# rat2.net
KiCad netlist of a schematic drawn in EAGLE
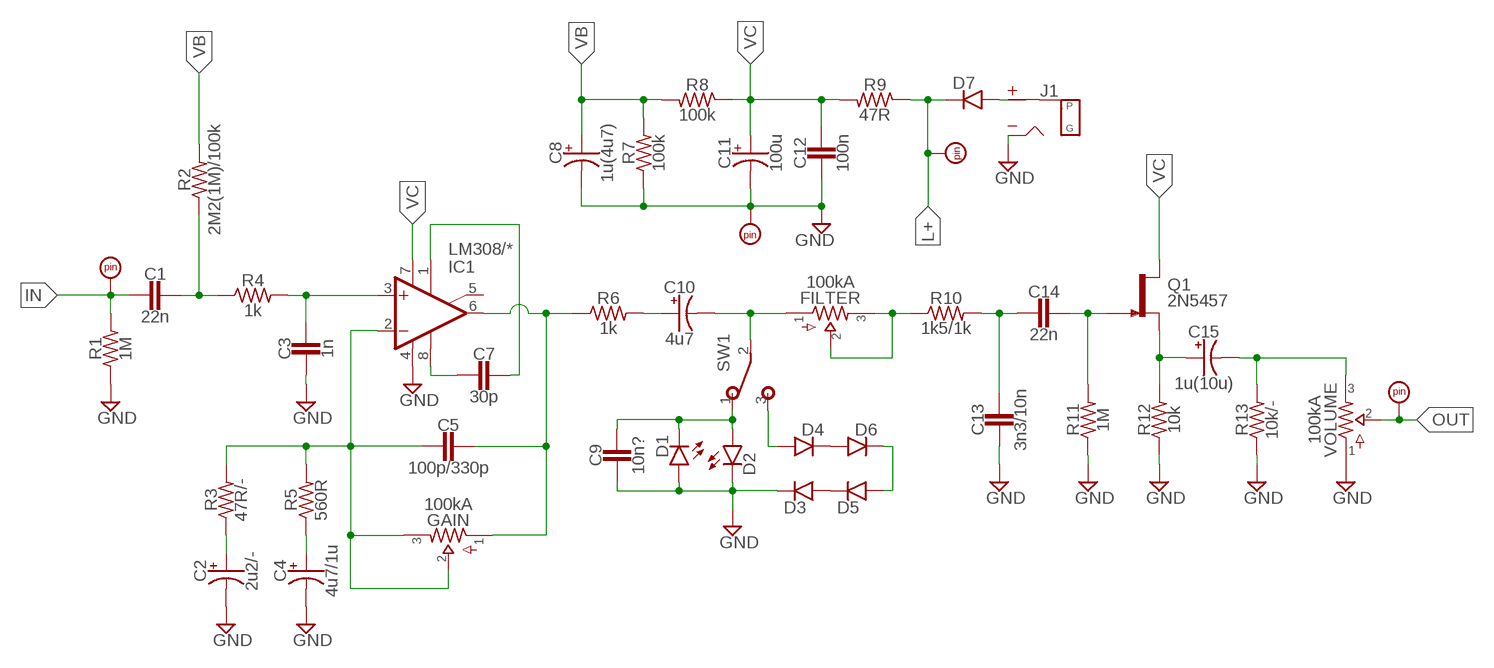
[diagram p0: schematic, sheet 1]

(export (version "E")
  (design (tool "Eeschema 10.0.6"))
  (components
    (comp (ref "C1")
      (value "22n")
      (footprint "eagle-import:050X030_025_2")
      (libsource (lib "eagle-import") (part "CER/FILM2"))
    )
    (comp (ref "C2")
      (value "2u2/-")
      (footprint "eagle-import:050_020_1")
      (libsource (lib "eagle-import") (part "0501"))
    )
    (comp (ref "C3")
      (value "1n")
      (footprint "eagle-import:050X030_025_2")
      (libsource (lib "eagle-import") (part "CER/FILM2"))
    )
    (comp (ref "C4")
      (value "4u7/1u")
      (footprint "eagle-import:050_020_1")
      (libsource (lib "eagle-import") (part "0501"))
    )
    (comp (ref "C5")
      (value "100p/330p")
      (footprint "eagle-import:050X030_025_2")
      (libsource (lib "eagle-import") (part "CER/FILM2"))
    )
    (comp (ref "C7")
      (value "30p")
      (footprint "eagle-import:050X030_025_2")
      (libsource (lib "eagle-import") (part "CER/FILM2"))
    )
    (comp (ref "C8")
      (value "1u(4u7)")
      (footprint "eagle-import:050_020_1")
      (libsource (lib "eagle-import") (part "0501"))
    )
    (comp (ref "C9")
      (value "10n?")
      (footprint "eagle-import:050X030_025_2")
      (libsource (lib "eagle-import") (part "CER/FILM2"))
    )
    (comp (ref "C10")
      (value "4u7")
      (footprint "eagle-import:050_020_1")
      (libsource (lib "eagle-import") (part "0501"))
    )
    (comp (ref "C11")
      (value "100u")
      (footprint "eagle-import:050_020_1")
      (libsource (lib "eagle-import") (part "0501"))
    )
    (comp (ref "C12")
      (value "100n")
      (footprint "eagle-import:050X030_025_2")
      (libsource (lib "eagle-import") (part "CER/FILM2"))
    )
    (comp (ref "C13")
      (value "3n3/10n")
      (footprint "eagle-import:050X030_025_2")
      (libsource (lib "eagle-import") (part "CER/FILM2"))
    )
    (comp (ref "C14")
      (value "22n")
      (footprint "eagle-import:050X030_025_2")
      (libsource (lib "eagle-import") (part "CER/FILM2"))
    )
    (comp (ref "C15")
      (value "1u(10u)")
      (footprint "eagle-import:050_020_1")
      (libsource (lib "eagle-import") (part "0501"))
    )
    (comp (ref "D1")
      (value "LEDB")
      (footprint "eagle-import:3MM_B")
      (libsource (lib "eagle-import") (part "LEDB"))
    )
    (comp (ref "D2")
      (value "LEDB")
      (footprint "eagle-import:3MM_B")
      (libsource (lib "eagle-import") (part "LEDB"))
    )
    (comp (ref "D3")
      (value "DO35.3")
      (footprint "eagle-import:DO35-3")
      (libsource (lib "eagle-import") (part "DO35.3"))
    )
    (comp (ref "D4")
      (value "DO35.3")
      (footprint "eagle-import:DO35-3")
      (libsource (lib "eagle-import") (part "DO35.3"))
    )
    (comp (ref "D5")
      (value "DO35.3")
      (footprint "eagle-import:DO35-3")
      (libsource (lib "eagle-import") (part "DO35.3"))
    )
    (comp (ref "D6")
      (value "DO35.3")
      (footprint "eagle-import:DO35-3")
      (libsource (lib "eagle-import") (part "DO35.3"))
    )
    (comp (ref "D7")
      (value "DO41.3")
      (footprint "eagle-import:DO41-3")
      (libsource (lib "eagle-import") (part "DO41.3"))
    )
    (comp (ref "FILTER")
      (value "100kA")
      (footprint "eagle-import:16MM")
      (libsource (lib "eagle-import") (part "POTS16MM"))
    )
    (comp (ref "GAIN")
      (value "100kA")
      (footprint "eagle-import:16MM")
      (libsource (lib "eagle-import") (part "POTS16MM"))
    )
    (comp (ref "IC1")
      (value "LM308/*")
      (footprint "eagle-import:DIL08")
      (libsource (lib "eagle-import") (part "SINGLETH"))
    )
    (comp (ref "J1")
      (value "DC_MONO")
      (footprint "eagle-import:DC")
      (libsource (lib "eagle-import") (part "DC_MONO"))
    )
    (comp (ref "PAD1")
      (value "PADSQR")
      (footprint "eagle-import:SQUARE")
      (libsource (lib "eagle-import") (part "PADSQR"))
    )
    (comp (ref "PAD2")
      (value "PADRND")
      (footprint "eagle-import:ROUND")
      (libsource (lib "eagle-import") (part "PADRND"))
    )
    (comp (ref "PAD3")
      (value "PADSQR")
      (footprint "eagle-import:SQUARE")
      (libsource (lib "eagle-import") (part "PADSQR"))
    )
    (comp (ref "PAD4")
      (value "PADSQR")
      (footprint "eagle-import:SQUARE")
      (libsource (lib "eagle-import") (part "PADSQR"))
    )
    (comp (ref "Q1")
      (value "2N5457")
      (footprint "eagle-import:TO92-")
      (libsource (lib "eagle-import") (part "2N5457"))
    )
    (comp (ref "R1")
      (value "1M")
      (footprint "eagle-import:R0207_3")
      (libsource (lib "eagle-import") (part "R_.3B"))
    )
    (comp (ref "R2")
      (value "2M2(1M)/100k")
      (footprint "eagle-import:R0207_3")
      (libsource (lib "eagle-import") (part "R_.3B"))
    )
    (comp (ref "R3")
      (value "47R/-")
      (footprint "eagle-import:R0207_3")
      (libsource (lib "eagle-import") (part "R_.3B"))
    )
    (comp (ref "R4")
      (value "1k")
      (footprint "eagle-import:R0207_3")
      (libsource (lib "eagle-import") (part "R_.3B"))
    )
    (comp (ref "R5")
      (value "560R")
      (footprint "eagle-import:R0207_3")
      (libsource (lib "eagle-import") (part "R_.3B"))
    )
    (comp (ref "R6")
      (value "1k")
      (footprint "eagle-import:R0207_3")
      (libsource (lib "eagle-import") (part "R_.3B"))
    )
    (comp (ref "R7")
      (value "100k")
      (footprint "eagle-import:R0207_3")
      (libsource (lib "eagle-import") (part "R_.3B"))
    )
    (comp (ref "R8")
      (value "100k")
      (footprint "eagle-import:R0207_3")
      (libsource (lib "eagle-import") (part "R_.3B"))
    )
    (comp (ref "R9")
      (value "47R")
      (footprint "eagle-import:R0207_3")
      (libsource (lib "eagle-import") (part "R_.3B"))
    )
    (comp (ref "R10")
      (value "1k5/1k")
      (footprint "eagle-import:R0207_3")
      (libsource (lib "eagle-import") (part "R_.3B"))
    )
    (comp (ref "R11")
      (value "1M")
      (footprint "eagle-import:R0207_3")
      (libsource (lib "eagle-import") (part "R_.3B"))
    )
    (comp (ref "R12")
      (value "10k")
      (footprint "eagle-import:R0207_3")
      (libsource (lib "eagle-import") (part "R_.3B"))
    )
    (comp (ref "R13")
      (value "10k/-")
      (footprint "eagle-import:R0207_3")
      (libsource (lib "eagle-import") (part "R_.3B"))
    )
    (comp (ref "SW1")
      (value "SPDT")
      (footprint "eagle-import:M9040P")
      (libsource (lib "eagle-import") (part "SPDT"))
    )
    (comp (ref "VOLUME")
      (value "100kA")
      (footprint "eagle-import:16MM")
      (libsource (lib "eagle-import") (part "POTS16MM"))
    )
  )
  (nets
    (net (code "1") (name "GND") (class "Default")
      (node (ref "C11") (pin "-") (pinfunction "-_-") (pintype "passive"))
      (node (ref "C12") (pin "2") (pinfunction "2_2") (pintype "passive"))
      (node (ref "C13") (pin "2") (pinfunction "2_2") (pintype "passive"))
      (node (ref "C2") (pin "-") (pinfunction "-_-") (pintype "passive"))
      (node (ref "C3") (pin "2") (pinfunction "2_2") (pintype "passive"))
      (node (ref "C4") (pin "-") (pinfunction "-_-") (pintype "passive"))
      (node (ref "C8") (pin "-") (pinfunction "-_-") (pintype "passive"))
      (node (ref "C9") (pin "2") (pinfunction "2_2") (pintype "passive"))
      (node (ref "D1") (pin "A") (pinfunction "A_A") (pintype "passive"))
      (node (ref "D2") (pin "K") (pinfunction "C_K") (pintype "passive"))
      (node (ref "D3") (pin "C") (pinfunction "C_C") (pintype "passive"))
      (node (ref "IC1") (pin "4") (pinfunction "V-_4") (pintype "power_in"))
      (node (ref "J1") (pin "S") (pinfunction "SLEEVE_S") (pintype "passive"))
      (node (ref "PAD2") (pin "1") (pinfunction "P$1_1") (pintype "bidirectional"))
      (node (ref "R1") (pin "1") (pinfunction "1_1") (pintype "passive"))
      (node (ref "R11") (pin "1") (pinfunction "1_1") (pintype "passive"))
      (node (ref "R12") (pin "1") (pinfunction "1_1") (pintype "passive"))
      (node (ref "R13") (pin "1") (pinfunction "1_1") (pintype "passive"))
      (node (ref "R7") (pin "1") (pinfunction "1_1") (pintype "passive"))
      (node (ref "VOLUME") (pin "1") (pinfunction "1_1") (pintype "passive"))
    )
    (net (code "2") (name "IN") (class "Default")
      (node (ref "C1") (pin "2") (pinfunction "2_2") (pintype "passive"))
      (node (ref "PAD1") (pin "1") (pinfunction "P$1_1") (pintype "bidirectional"))
      (node (ref "R1") (pin "2") (pinfunction "2_2") (pintype "passive"))
    )
    (net (code "3") (name "L+") (class "Default")
      (node (ref "D7") (pin "C") (pinfunction "C_C") (pintype "passive"))
      (node (ref "PAD3") (pin "1") (pinfunction "P$1_1") (pintype "bidirectional"))
      (node (ref "R9") (pin "1") (pinfunction "1_1") (pintype "passive"))
    )
    (net (code "4") (name "Net-(C1-Pad1)") (class "Default")
      (node (ref "C1") (pin "1") (pinfunction "1_1") (pintype "passive"))
      (node (ref "R2") (pin "1") (pinfunction "1_1") (pintype "passive"))
      (node (ref "R4") (pin "1") (pinfunction "1_1") (pintype "passive"))
    )
    (net (code "5") (name "Net-(C2-Pad+)") (class "Default")
      (node (ref "C2") (pin "+") (pinfunction "+_+") (pintype "passive"))
      (node (ref "R3") (pin "1") (pinfunction "1_1") (pintype "passive"))
    )
    (net (code "6") (name "Net-(C4-Pad+)") (class "Default")
      (node (ref "C4") (pin "+") (pinfunction "+_+") (pintype "passive"))
      (node (ref "R5") (pin "1") (pinfunction "1_1") (pintype "passive"))
    )
    (net (code "7") (name "Net-(C10-Pad+)") (class "Default")
      (node (ref "C10") (pin "+") (pinfunction "+_+") (pintype "passive"))
      (node (ref "R6") (pin "2") (pinfunction "2_2") (pintype "passive"))
    )
    (net (code "8") (name "Net-(C13-Pad1)") (class "Default")
      (node (ref "C13") (pin "1") (pinfunction "1_1") (pintype "passive"))
      (node (ref "C14") (pin "2") (pinfunction "2_2") (pintype "passive"))
      (node (ref "R10") (pin "2") (pinfunction "2_2") (pintype "passive"))
    )
    (net (code "9") (name "Net-(C15-Pad-)") (class "Default")
      (node (ref "C15") (pin "-") (pinfunction "-_-") (pintype "passive"))
      (node (ref "R13") (pin "2") (pinfunction "2_2") (pintype "passive"))
      (node (ref "VOLUME") (pin "3") (pinfunction "3_3") (pintype "passive"))
    )
    (net (code "10") (name "Net-(D1-C)") (class "Default")
      (node (ref "C9") (pin "1") (pinfunction "1_1") (pintype "passive"))
      (node (ref "D1") (pin "K") (pinfunction "C_K") (pintype "passive"))
      (node (ref "D2") (pin "A") (pinfunction "A_A") (pintype "passive"))
      (node (ref "SW1") (pin "1") (pinfunction "O_1") (pintype "passive"))
    )
    (net (code "11") (name "Net-(D3-PadA)") (class "Default")
      (node (ref "D3") (pin "A") (pinfunction "A_A") (pintype "passive"))
      (node (ref "D5") (pin "C") (pinfunction "C_C") (pintype "passive"))
    )
    (net (code "12") (name "Net-(D4-PadC)") (class "Default")
      (node (ref "D4") (pin "C") (pinfunction "C_C") (pintype "passive"))
      (node (ref "D6") (pin "A") (pinfunction "A_A") (pintype "passive"))
    )
    (net (code "13") (name "Net-(D5-PadA)") (class "Default")
      (node (ref "D5") (pin "A") (pinfunction "A_A") (pintype "passive"))
      (node (ref "D6") (pin "C") (pinfunction "C_C") (pintype "passive"))
    )
    (net (code "14") (name "Net-(FILTER-Pad2)") (class "Default")
      (node (ref "FILTER") (pin "2") (pinfunction "2_2") (pintype "passive"))
      (node (ref "FILTER") (pin "3") (pinfunction "3_3") (pintype "passive"))
      (node (ref "R10") (pin "1") (pinfunction "1_1") (pintype "passive"))
    )
    (net (code "15") (name "Net-(IC1-+IN)") (class "Default")
      (node (ref "C3") (pin "1") (pinfunction "1_1") (pintype "passive"))
      (node (ref "IC1") (pin "3") (pinfunction "+IN_3") (pintype "input"))
      (node (ref "R4") (pin "2") (pinfunction "2_2") (pintype "passive"))
    )
    (net (code "16") (name "Net-(IC1--IN)") (class "Default")
      (node (ref "C5") (pin "2") (pinfunction "2_2") (pintype "passive"))
      (node (ref "GAIN") (pin "2") (pinfunction "2_2") (pintype "passive"))
      (node (ref "GAIN") (pin "3") (pinfunction "3_3") (pintype "passive"))
      (node (ref "IC1") (pin "2") (pinfunction "-IN_2") (pintype "input"))
      (node (ref "R3") (pin "2") (pinfunction "2_2") (pintype "passive"))
      (node (ref "R5") (pin "2") (pinfunction "2_2") (pintype "passive"))
    )
    (net (code "17") (name "Net-(IC1-ON1)") (class "Default")
      (node (ref "C7") (pin "1") (pinfunction "1_1") (pintype "passive"))
      (node (ref "IC1") (pin "1") (pinfunction "ON1_1") (pintype "passive"))
    )
    (net (code "18") (name "Net-(IC1-OPT)") (class "Default")
      (node (ref "C7") (pin "2") (pinfunction "2_2") (pintype "passive"))
      (node (ref "IC1") (pin "8") (pinfunction "OPT_8") (pintype "passive"))
    )
    (net (code "19") (name "Net-(IC1-OUT)") (class "Default")
      (node (ref "C5") (pin "1") (pinfunction "1_1") (pintype "passive"))
      (node (ref "GAIN") (pin "1") (pinfunction "1_1") (pintype "passive"))
      (node (ref "IC1") (pin "6") (pinfunction "OUT_6") (pintype "output"))
      (node (ref "R6") (pin "1") (pinfunction "1_1") (pintype "passive"))
    )
    (net (code "20") (name "Net-(J1-TIP)") (class "Default")
      (node (ref "D7") (pin "A") (pinfunction "A_A") (pintype "passive"))
      (node (ref "J1") (pin "T") (pinfunction "TIP_T") (pintype "passive"))
    )
    (net (code "21") (name "Net-(Q1-G)") (class "Default")
      (node (ref "C14") (pin "1") (pinfunction "1_1") (pintype "passive"))
      (node (ref "Q1") (pin "1") (pinfunction "G_1") (pintype "passive"))
      (node (ref "R11") (pin "2") (pinfunction "2_2") (pintype "passive"))
    )
    (net (code "22") (name "Net-(Q1-S)") (class "Default")
      (node (ref "C15") (pin "+") (pinfunction "+_+") (pintype "passive"))
      (node (ref "Q1") (pin "2") (pinfunction "S_2") (pintype "passive"))
      (node (ref "R12") (pin "2") (pinfunction "2_2") (pintype "passive"))
    )
    (net (code "23") (name "Net-(SW1-P)") (class "Default")
      (node (ref "C10") (pin "-") (pinfunction "-_-") (pintype "passive"))
      (node (ref "FILTER") (pin "1") (pinfunction "1_1") (pintype "passive"))
      (node (ref "SW1") (pin "2") (pinfunction "P_2") (pintype "passive"))
    )
    (net (code "24") (name "Net-(SW1-S)") (class "Default")
      (node (ref "D4") (pin "A") (pinfunction "A_A") (pintype "passive"))
      (node (ref "SW1") (pin "3") (pinfunction "S_3") (pintype "passive"))
    )
    (net (code "25") (name "OUT") (class "Default")
      (node (ref "PAD4") (pin "1") (pinfunction "P$1_1") (pintype "bidirectional"))
      (node (ref "VOLUME") (pin "2") (pinfunction "2_2") (pintype "passive"))
    )
    (net (code "26") (name "VB") (class "Default")
      (node (ref "C8") (pin "+") (pinfunction "+_+") (pintype "passive"))
      (node (ref "R2") (pin "2") (pinfunction "2_2") (pintype "passive"))
      (node (ref "R7") (pin "2") (pinfunction "2_2") (pintype "passive"))
      (node (ref "R8") (pin "2") (pinfunction "2_2") (pintype "passive"))
    )
    (net (code "27") (name "VC") (class "Default")
      (node (ref "C11") (pin "+") (pinfunction "+_+") (pintype "passive"))
      (node (ref "C12") (pin "1") (pinfunction "1_1") (pintype "passive"))
      (node (ref "IC1") (pin "7") (pinfunction "V+_7") (pintype "power_in"))
      (node (ref "Q1") (pin "3") (pinfunction "D_3") (pintype "passive"))
      (node (ref "R8") (pin "1") (pinfunction "1_1") (pintype "passive"))
      (node (ref "R9") (pin "2") (pinfunction "2_2") (pintype "passive"))
    )
    (net (code "28") (name "unconnected-(IC1-ON2-Pad5)") (class "Default")
      (node (ref "IC1") (pin "5") (pinfunction "ON2_5") (pintype "passive"))
    )
  )
)
